# invader-rgb_working.net
KiCad netlist of a schematic drawn in EAGLE
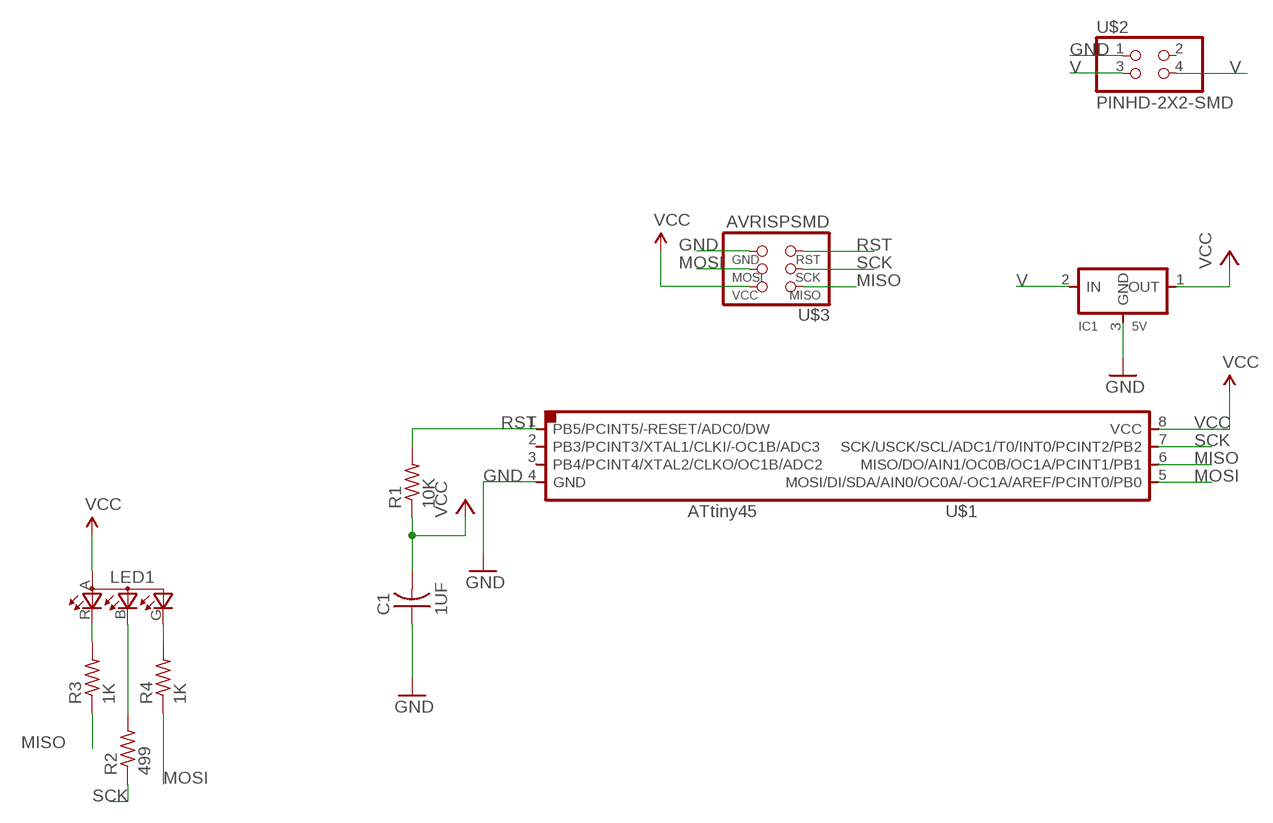
[diagram p0: schematic, sheet 1]

(export (version "E")
  (design (tool "Eeschema 10.0.6"))
  (components
    (comp (ref "C1")
      (value "1UF")
      (footprint "eagle-import:C1206FAB")
      (libsource (lib "eagle-import") (part "CAP-US1206FAB"))
    )
    (comp (ref "IC1")
      (value "5V")
      (footprint "eagle-import:SOT23")
      (libsource (lib "eagle-import") (part "REGULATORSOT23"))
    )
    (comp (ref "LED1")
      (value "LEDRGBOLD")
      (footprint "eagle-import:P-LCC-4-3")
      (libsource (lib "eagle-import") (part "LEDRGBOLD"))
    )
    (comp (ref "R1")
      (value "10K")
      (footprint "eagle-import:R1206FAB")
      (libsource (lib "eagle-import") (part "RES-US1206FAB"))
    )
    (comp (ref "R2")
      (value "499")
      (footprint "eagle-import:R1206FAB")
      (libsource (lib "eagle-import") (part "RES-US1206FAB"))
    )
    (comp (ref "R3")
      (value "1K")
      (footprint "eagle-import:R1206FAB")
      (libsource (lib "eagle-import") (part "RES-US1206FAB"))
    )
    (comp (ref "R4")
      (value "1K")
      (footprint "eagle-import:R1206FAB")
      (libsource (lib "eagle-import") (part "RES-US1206FAB"))
    )
    (comp (ref "U$1")
      (value "ATTINY45SI")
      (footprint "eagle-import:SOIC8")
      (libsource (lib "eagle-import") (part "ATTINY45SI"))
    )
    (comp (ref "U$2")
      (value "PINHD-2X2-SMD")
      (footprint "eagle-import:2X02SMD")
      (libsource (lib "eagle-import") (part "PINHD-2X2-SMD"))
    )
    (comp (ref "U$3")
      (value "AVRISPSMD")
      (footprint "eagle-import:2X03SMD")
      (libsource (lib "eagle-import") (part "AVRISPSMD"))
    )
  )
  (nets
    (net (code "1") (name "/MISO") (class "Default")
      (node (ref "R3") (pin "1") (pinfunction "1_1") (pintype "passive"))
      (node (ref "U$1") (pin "6") (pinfunction "MISO/DO/AIN1/OC0B/OC1A/PCINT1/PB1_6") (pintype "bidirectional"))
      (node (ref "U$3") (pin "1") (pinfunction "MISO_1") (pintype "passive"))
    )
    (net (code "2") (name "/MOSI") (class "Default")
      (node (ref "R4") (pin "1") (pinfunction "1_1") (pintype "passive"))
      (node (ref "U$1") (pin "5") (pinfunction "MOSI/DI/SDA/AIN0/OC0A/-OC1A/AREF/PCINT0/PB0_5") (pintype "bidirectional"))
      (node (ref "U$3") (pin "4") (pinfunction "MOSI_4") (pintype "passive"))
    )
    (net (code "3") (name "/RST") (class "Default")
      (node (ref "R1") (pin "2") (pinfunction "2_2") (pintype "passive"))
      (node (ref "U$1") (pin "1") (pinfunction "PB5/PCINT5/-RESET/ADC0/DW_1") (pintype "bidirectional"))
      (node (ref "U$3") (pin "5") (pinfunction "RST_5") (pintype "passive"))
    )
    (net (code "4") (name "/SCK") (class "Default")
      (node (ref "R2") (pin "1") (pinfunction "1_1") (pintype "passive"))
      (node (ref "U$1") (pin "7") (pinfunction "SCK/USCK/SCL/ADC1/T0/INT0/PCINT2/PB2_7") (pintype "bidirectional"))
      (node (ref "U$3") (pin "3") (pinfunction "SCK_3") (pintype "passive"))
    )
    (net (code "5") (name "/V") (class "Default")
      (node (ref "IC1") (pin "2") (pinfunction "IN_2") (pintype "bidirectional"))
      (node (ref "U$2") (pin "3") (pinfunction "3_3") (pintype "passive"))
      (node (ref "U$2") (pin "4") (pinfunction "4_4") (pintype "passive"))
    )
    (net (code "6") (name "GND") (class "Default")
      (node (ref "C1") (pin "1") (pinfunction "1_1") (pintype "passive"))
      (node (ref "IC1") (pin "3") (pinfunction "GND_3") (pintype "bidirectional"))
      (node (ref "U$1") (pin "4") (pinfunction "GND_4") (pintype "bidirectional"))
      (node (ref "U$2") (pin "1") (pinfunction "1_1") (pintype "passive"))
      (node (ref "U$3") (pin "6") (pinfunction "GND_6") (pintype "passive"))
    )
    (net (code "7") (name "Net-(LED1-CBLUE)") (class "Default")
      (node (ref "LED1") (pin "B") (pinfunction "CBLUE_B") (pintype "passive"))
      (node (ref "R2") (pin "2") (pinfunction "2_2") (pintype "passive"))
    )
    (net (code "8") (name "Net-(LED1-CGREEN)") (class "Default")
      (node (ref "LED1") (pin "G") (pinfunction "CGREEN_G") (pintype "passive"))
      (node (ref "R4") (pin "2") (pinfunction "2_2") (pintype "passive"))
    )
    (net (code "9") (name "Net-(LED1-CRED)") (class "Default")
      (node (ref "LED1") (pin "R") (pinfunction "CRED_R") (pintype "passive"))
      (node (ref "R3") (pin "2") (pinfunction "2_2") (pintype "passive"))
    )
    (net (code "10") (name "VCC") (class "Default")
      (node (ref "C1") (pin "2") (pinfunction "2_2") (pintype "passive"))
      (node (ref "IC1") (pin "1") (pinfunction "OUT_1") (pintype "bidirectional"))
      (node (ref "LED1") (pin "A") (pinfunction "A2_A") (pintype "passive"))
      (node (ref "R1") (pin "1") (pinfunction "1_1") (pintype "passive"))
      (node (ref "U$1") (pin "8") (pinfunction "VCC_8") (pintype "bidirectional"))
      (node (ref "U$3") (pin "2") (pinfunction "VCC_2") (pintype "passive"))
    )
    (net (code "11") (name "unconnected-(U$1-PB3{slash}PCINT3{slash}XTAL1{slash}CLKI{slash}-OC1B{slash}ADC3-Pad2)") (class "Default")
      (node (ref "U$1") (pin "2") (pinfunction "PB3/PCINT3/XTAL1/CLKI/-OC1B/ADC3_2") (pintype "bidirectional"))
    )
    (net (code "12") (name "unconnected-(U$1-PB4{slash}PCINT4{slash}XTAL2{slash}CLKO{slash}OC1B{slash}ADC2-Pad3)") (class "Default")
      (node (ref "U$1") (pin "3") (pinfunction "PB4/PCINT4/XTAL2/CLKO/OC1B/ADC2_3") (pintype "bidirectional"))
    )
    (net (code "13") (name "unconnected-(U$2-Pad2)") (class "Default")
      (node (ref "U$2") (pin "2") (pinfunction "2_2") (pintype "passive"))
    )
  )
)
